# SparkFun_Thing_Plus_ESP32_WROOM_C.net
KiCad netlist of a schematic drawn in EAGLE
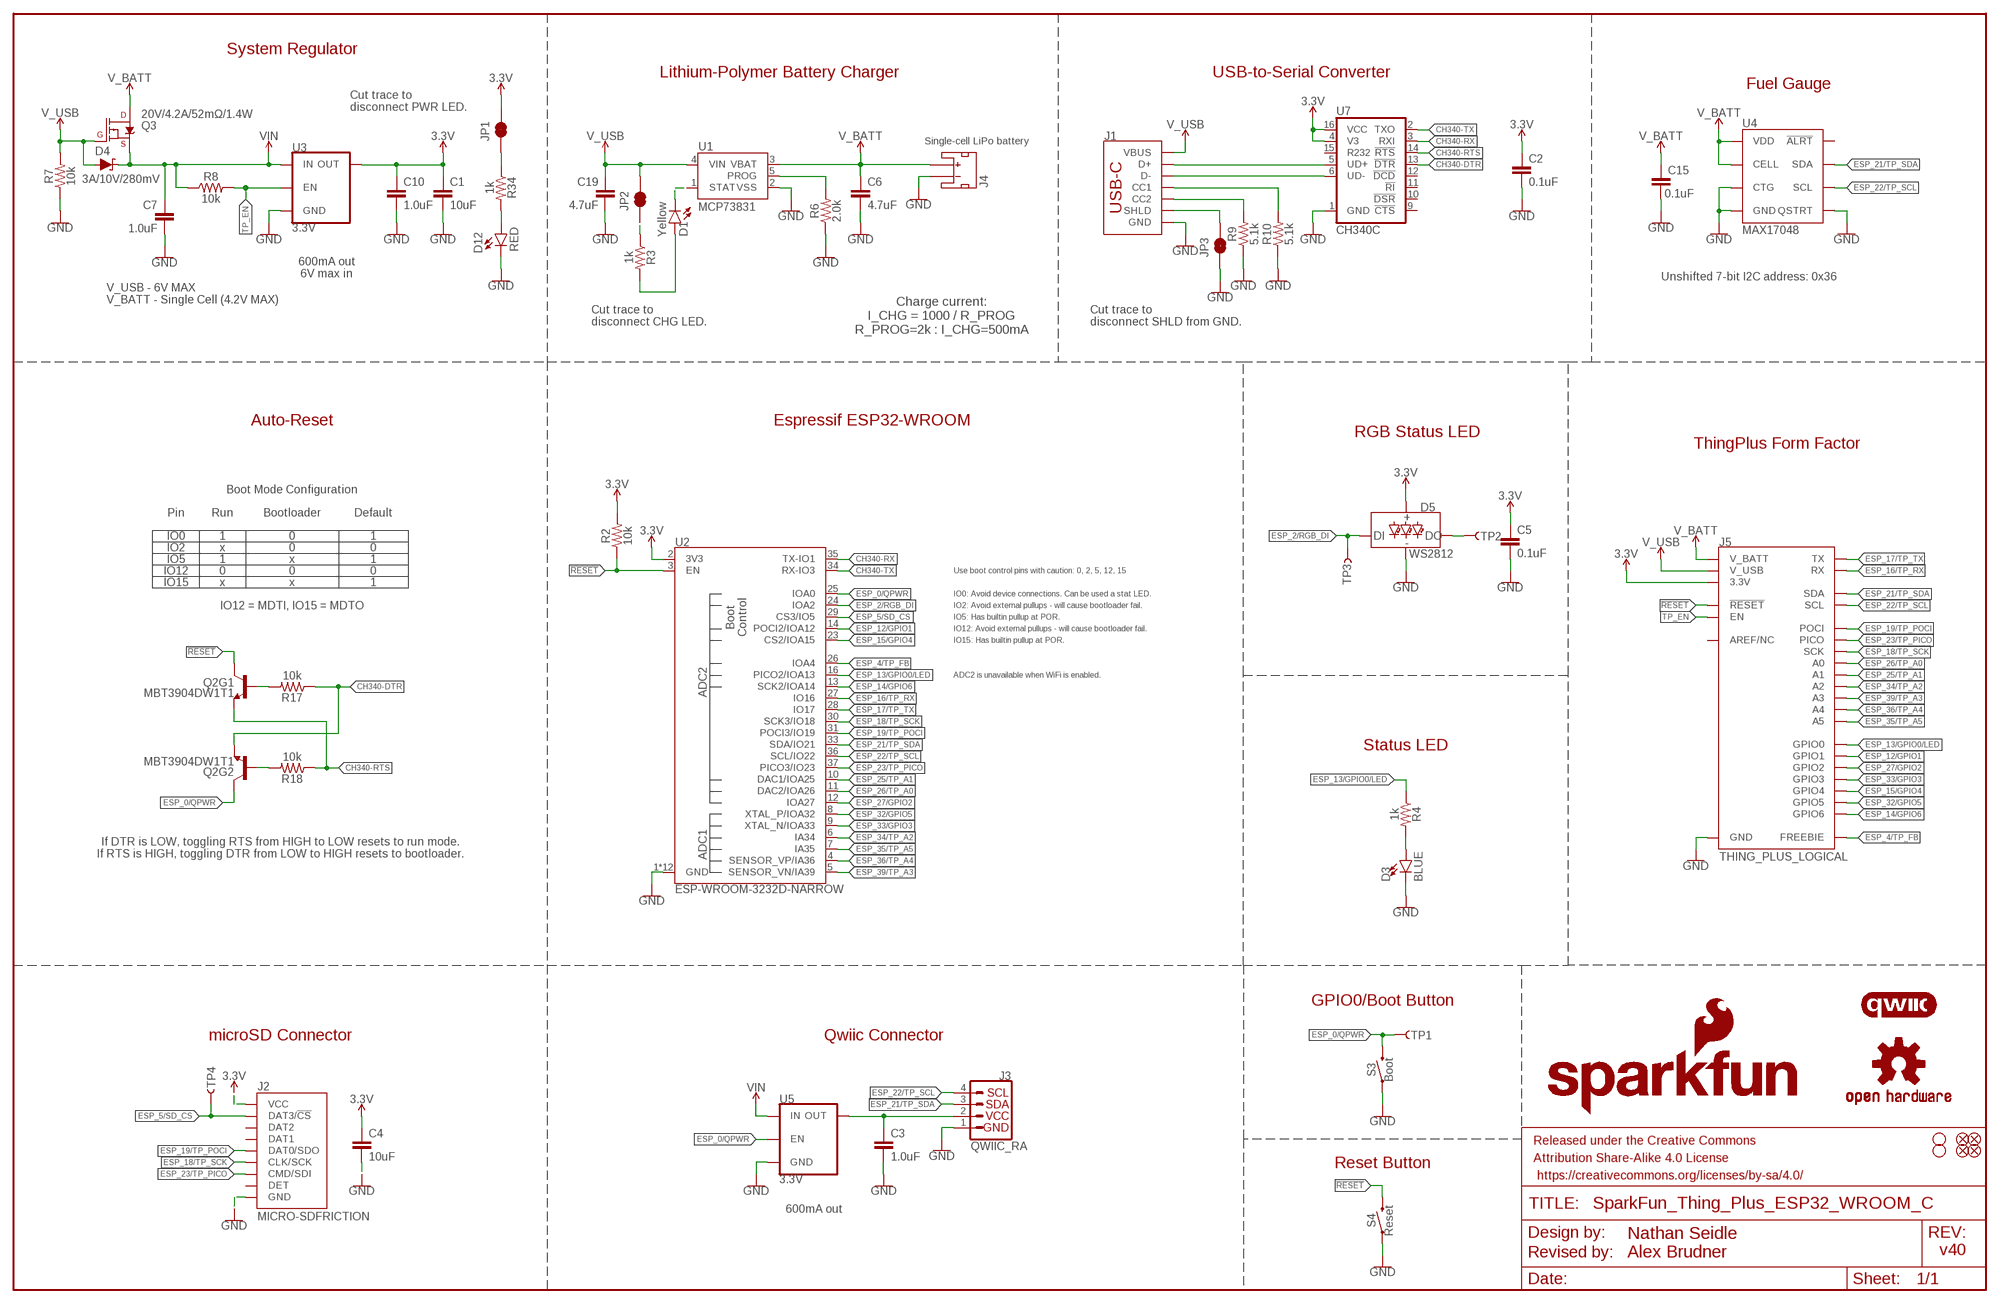
[diagram p0: schematic, sheet 1]

(export (version "E")
  (design (tool "Eeschema 10.0.6"))
  (components
    (comp (ref "C1")
      (value "10uF")
      (footprint "eagle-import:0402-TIGHT")
      (libsource (lib "eagle-import") (part "10UF-0402T-6.3V-20%"))
    )
    (comp (ref "C2")
      (value "0.1uF")
      (footprint "eagle-import:0402-TIGHT")
      (libsource (lib "eagle-import") (part "0.1UF-0402T-6.3V-10%-X7R"))
    )
    (comp (ref "C3")
      (value "1.0uF")
      (footprint "eagle-import:0402-TIGHT")
      (libsource (lib "eagle-import") (part "1.0UF-0402T-16V-10%"))
    )
    (comp (ref "C4")
      (value "10uF")
      (footprint "eagle-import:0402-TIGHT")
      (libsource (lib "eagle-import") (part "10UF-0402T-6.3V-20%"))
    )
    (comp (ref "C5")
      (value "0.1uF")
      (footprint "eagle-import:0402-TIGHT")
      (libsource (lib "eagle-import") (part "0.1UF-0402T-6.3V-10%-X7R"))
    )
    (comp (ref "C6")
      (value "4.7uF")
      (footprint "eagle-import:0402-TIGHT")
      (libsource (lib "eagle-import") (part "4.7UF-0402_TIGHT-6.3V-20%-X5R"))
    )
    (comp (ref "C7")
      (value "1.0uF")
      (footprint "eagle-import:0402-TIGHT")
      (libsource (lib "eagle-import") (part "1.0UF-0402T-16V-10%"))
    )
    (comp (ref "C10")
      (value "1.0uF")
      (footprint "eagle-import:0402-TIGHT")
      (libsource (lib "eagle-import") (part "1.0UF-0402T-16V-10%"))
    )
    (comp (ref "C15")
      (value "0.1uF")
      (footprint "eagle-import:0402-TIGHT")
      (libsource (lib "eagle-import") (part "0.1UF-0402T-16V-10%"))
    )
    (comp (ref "C19")
      (value "4.7uF")
      (footprint "eagle-import:0603")
      (libsource (lib "eagle-import") (part "4.7UF-0603-35V-(20%)"))
    )
    (comp (ref "D1")
      (value "Yellow")
      (footprint "eagle-import:LED-0603")
      (libsource (lib "eagle-import") (part "LED-YELLOW0603"))
    )
    (comp (ref "D3")
      (value "BLUE")
      (footprint "eagle-import:LED-0603")
      (libsource (lib "eagle-import") (part "LED-BLUE0603"))
    )
    (comp (ref "D4")
      (value "3A/10V/280mV")
      (footprint "eagle-import:SOD-323")
      (libsource (lib "eagle-import") (part "DIODE-SCHOTTKY-BAT60A"))
    )
    (comp (ref "D5")
      (value "WS2812")
      (footprint "eagle-import:WS2812-2020")
      (libsource (lib "eagle-import") (part "WS2812_2020"))
    )
    (comp (ref "D12")
      (value "RED")
      (footprint "eagle-import:LED-0603")
      (libsource (lib "eagle-import") (part "LED-RED0603"))
    )
    (comp (ref "FD1")
      (value "FIDUCIALUFIDUCIAL")
      (footprint "eagle-import:FIDUCIAL-MICRO")
      (libsource (lib "eagle-import") (part "FIDUCIALUFIDUCIAL"))
    )
    (comp (ref "FD2")
      (value "FIDUCIALUFIDUCIAL")
      (footprint "eagle-import:FIDUCIAL-MICRO")
      (libsource (lib "eagle-import") (part "FIDUCIALUFIDUCIAL"))
    )
    (comp (ref "FD3")
      (value "FIDUCIALUFIDUCIAL")
      (footprint "eagle-import:FIDUCIAL-MICRO")
      (libsource (lib "eagle-import") (part "FIDUCIALUFIDUCIAL"))
    )
    (comp (ref "FD4")
      (value "FIDUCIALUFIDUCIAL")
      (footprint "eagle-import:FIDUCIAL-MICRO")
      (libsource (lib "eagle-import") (part "FIDUCIALUFIDUCIAL"))
    )
    (comp (ref "FRAME1")
      (value "FRAME-LEDGER")
      (footprint "eagle-import:CREATIVE_COMMONS")
      (fields
        (field (name "DESIGNER") "Nathan Seidle")
        (field (name "REV_BY") "Revised by:")
        (field (name "REV_DES") "Alex Brudner")
      )
      (libsource (lib "eagle-import") (part "FRAME-LEDGER"))
    )
    (comp (ref "H1")
      (value "STAND-OFFTIGHT")
      (footprint "eagle-import:STAND-OFF-TIGHT")
      (libsource (lib "eagle-import") (part "STAND-OFFTIGHT"))
    )
    (comp (ref "H2")
      (value "STAND-OFFTIGHT")
      (footprint "eagle-import:STAND-OFF-TIGHT")
      (libsource (lib "eagle-import") (part "STAND-OFFTIGHT"))
    )
    (comp (ref "J1")
      (value "USB_C_2-LAYER_PADS")
      (footprint "eagle-import:USB-C-16P-2LAYER-PADS")
      (libsource (lib "eagle-import") (part "USB_C_2-LAYER_PADS"))
    )
    (comp (ref "J2")
      (value "MICRO-SDFRICTION")
      (footprint "eagle-import:MICROSD_TINY")
      (libsource (lib "eagle-import") (part "MICRO-SDFRICTION"))
    )
    (comp (ref "J3")
      (value "QWIIC_RA")
      (footprint "eagle-import:JST04_1MM_RA")
      (libsource (lib "eagle-import") (part "QWIIC_CONNECTORJS-1MM"))
    )
    (comp (ref "J4")
      (value "JST_2MM_MALE")
      (footprint "eagle-import:JST-2-SMD")
      (libsource (lib "eagle-import") (part "JST_2MM_MALE"))
    )
    (comp (ref "J5")
      (value "THING_PLUS_LOGICAL")
      (footprint "eagle-import:THING_PLUS")
      (libsource (lib "eagle-import") (part "THING_PLUS_LOGICAL"))
    )
    (comp (ref "JP1")
      (value "JUMPER-SMT_2_NC_TRACE_SILK")
      (footprint "eagle-import:SMT-JUMPER_2_NC_TRACE_SILK")
      (libsource (lib "eagle-import") (part "JUMPER-SMT_2_NC_TRACE_SILK"))
    )
    (comp (ref "JP2")
      (value "JUMPER-SMT_2_NC_TRACE_SILK")
      (footprint "eagle-import:SMT-JUMPER_2_NC_TRACE_SILK")
      (libsource (lib "eagle-import") (part "JUMPER-SMT_2_NC_TRACE_SILK"))
    )
    (comp (ref "JP3")
      (value "JUMPER-SMT_2_NC_TRACE_SILK")
      (footprint "eagle-import:SMT-JUMPER_2_NC_TRACE_SILK")
      (libsource (lib "eagle-import") (part "JUMPER-SMT_2_NC_TRACE_SILK"))
    )
    (comp (ref "LOGO1")
      (value "SFE_LOGO_NAME_FLAME.1_INCH")
      (footprint "eagle-import:SFE_LOGO_NAME_FLAME_.1")
      (libsource (lib "eagle-import") (part "SFE_LOGO_NAME_FLAME.1_INCH"))
    )
    (comp (ref "LOGO2")
      (value "OSHW-LOGOMINI")
      (footprint "eagle-import:OSHW-LOGO-MINI")
      (libsource (lib "eagle-import") (part "OSHW-LOGOMINI"))
    )
    (comp (ref "LOGO4")
      (value "QWIIC_LOGO_4MM")
      (footprint "eagle-import:QWIIC_4MM")
      (libsource (lib "eagle-import") (part "QWIIC_LOGO_4MM"))
    )
    (comp (ref "Q2")
      (value "MBT3904DW1T1")
      (footprint "eagle-import:SC70-6")
      (libsource (lib "eagle-import") (part "TRANS_NPN_DUAL-MBT3904DW1T1"))
    )
    (comp (ref "Q3")
      (value "20V/4.2A/52mΩ/1.4W")
      (footprint "eagle-import:SOT23-3")
      (libsource (lib "eagle-import") (part "MOSFET_PCH-DMG2305UX-7"))
    )
    (comp (ref "R2")
      (value "10k")
      (footprint "eagle-import:0402-TIGHT")
      (libsource (lib "eagle-import") (part "10KOHM-0402T-1/16W-1%"))
    )
    (comp (ref "R3")
      (value "1k")
      (footprint "eagle-import:0402-TIGHT")
      (libsource (lib "eagle-import") (part "1KOHM-0402T-1/16W-1%"))
    )
    (comp (ref "R4")
      (value "1k")
      (footprint "eagle-import:0402-TIGHT")
      (libsource (lib "eagle-import") (part "1KOHM-0402T-1/16W-1%"))
    )
    (comp (ref "R6")
      (value "2.0k")
      (footprint "eagle-import:0603")
      (libsource (lib "eagle-import") (part "2.0KOHM-0603-1/10W-5%"))
    )
    (comp (ref "R7")
      (value "10k")
      (footprint "eagle-import:0402-TIGHT")
      (libsource (lib "eagle-import") (part "10KOHM-0402T-1/16W-1%"))
    )
    (comp (ref "R8")
      (value "10k")
      (footprint "eagle-import:0402-TIGHT")
      (libsource (lib "eagle-import") (part "10KOHM-0402T-1/16W-1%"))
    )
    (comp (ref "R9")
      (value "5.1k")
      (footprint "eagle-import:0402-TIGHT")
      (libsource (lib "eagle-import") (part "5.1KOHM-0402T-1/16W-1%"))
    )
    (comp (ref "R10")
      (value "5.1k")
      (footprint "eagle-import:0402-TIGHT")
      (libsource (lib "eagle-import") (part "5.1KOHM-0402T-1/16W-1%"))
    )
    (comp (ref "R17")
      (value "10k")
      (footprint "eagle-import:0402-TIGHT")
      (libsource (lib "eagle-import") (part "10KOHM-0402T-1/16W-1%"))
    )
    (comp (ref "R18")
      (value "10k")
      (footprint "eagle-import:0402-TIGHT")
      (libsource (lib "eagle-import") (part "10KOHM-0402T-1/16W-1%"))
    )
    (comp (ref "R34")
      (value "1k")
      (footprint "eagle-import:0402-TIGHT")
      (libsource (lib "eagle-import") (part "1KOHM-0402T-1/16W-1%"))
    )
    (comp (ref "S3")
      (value "Boot")
      (footprint "eagle-import:TACTILE_SWITCH_SMD_4.6X2.8MM")
      (libsource (lib "eagle-import") (part "MOMENTARY-SWITCH-SPST-SMD-4.6X2.8MM"))
    )
    (comp (ref "S4")
      (value "Reset")
      (footprint "eagle-import:TACTILE_SWITCH_SMD_4.6X2.8MM")
      (libsource (lib "eagle-import") (part "MOMENTARY-SWITCH-SPST-SMD-4.6X2.8MM"))
    )
    (comp (ref "TP1")
      (value "TEST-POINT3X5")
      (footprint "eagle-import:PAD.03X.05")
      (libsource (lib "eagle-import") (part "TEST-POINT3X5"))
    )
    (comp (ref "TP2")
      (value "TEST-POINT3X5")
      (footprint "eagle-import:PAD.03X.05")
      (libsource (lib "eagle-import") (part "TEST-POINT3X5"))
    )
    (comp (ref "TP3")
      (value "TEST-POINT3X5")
      (footprint "eagle-import:PAD.03X.05")
      (libsource (lib "eagle-import") (part "TEST-POINT3X5"))
    )
    (comp (ref "TP4")
      (value "TEST-POINT3X5")
      (footprint "eagle-import:PAD.03X.05")
      (libsource (lib "eagle-import") (part "TEST-POINT3X5"))
    )
    (comp (ref "U1")
      (value "MCP73831")
      (footprint "eagle-import:SOT23-5")
      (libsource (lib "eagle-import") (part "MCP73831"))
    )
    (comp (ref "U2")
      (value "ESP-WROOM-3232D-NARROW")
      (footprint "eagle-import:ESP-WROOM-32D-NARROW")
      (libsource (lib "eagle-import") (part "ESP-WROOM-3232D-NARROW"))
    )
    (comp (ref "U3")
      (value "3.3V")
      (footprint "eagle-import:SOT23-5")
      (libsource (lib "eagle-import") (part "V_REG_AP2112K-3.3V"))
    )
    (comp (ref "U4")
      (value "MAX17048")
      (footprint "eagle-import:DFN-8")
      (libsource (lib "eagle-import") (part "MAX17048DFN8"))
    )
    (comp (ref "U5")
      (value "3.3V")
      (footprint "eagle-import:SOT23-5")
      (libsource (lib "eagle-import") (part "V_REG_AP2112K-3.3V"))
    )
    (comp (ref "U7")
      (value "CH340C")
      (footprint "eagle-import:SO016")
      (libsource (lib "eagle-import") (part "CH340C"))
    )
  )
  (nets
    (net (code "1") (name "/~{RESET}") (class "Default")
      (node (ref "J5") (pin "28") (pinfunction "~{RESET}_28") (pintype "bidirectional"))
      (node (ref "Q2") (pin "3") (pinfunction "C_3") (pintype "passive"))
      (node (ref "R2") (pin "1") (pinfunction "1_1") (pintype "passive"))
      (node (ref "S4") (pin "3") (pinfunction "2_3") (pintype "passive"))
      (node (ref "S4") (pin "4") (pinfunction "2_4") (pintype "passive"))
      (node (ref "U2") (pin "3") (pinfunction "EN_3") (pintype "bidirectional"))
    )
    (net (code "2") (name "3.3V") (class "Default")
      (node (ref "C1") (pin "1") (pinfunction "1_1") (pintype "passive"))
      (node (ref "C10") (pin "1") (pinfunction "1_1") (pintype "passive"))
      (node (ref "C2") (pin "1") (pinfunction "1_1") (pintype "passive"))
      (node (ref "C4") (pin "1") (pinfunction "1_1") (pintype "passive"))
      (node (ref "C5") (pin "1") (pinfunction "1_1") (pintype "passive"))
      (node (ref "D5") (pin "VCC") (pinfunction "VCC_VCC") (pintype "bidirectional"))
      (node (ref "J2") (pin "4") (pinfunction "VCC_4") (pintype "bidirectional"))
      (node (ref "J5") (pin "27") (pinfunction "3.3V_27") (pintype "bidirectional"))
      (node (ref "JP1") (pin "2") (pinfunction "2_2") (pintype "passive"))
      (node (ref "R2") (pin "2") (pinfunction "2_2") (pintype "passive"))
      (node (ref "U2") (pin "2") (pinfunction "3V3_2") (pintype "bidirectional"))
      (node (ref "U3") (pin "5") (pinfunction "OUT_5") (pintype "passive"))
      (node (ref "U7") (pin "16") (pinfunction "VCC_16") (pintype "bidirectional"))
      (node (ref "U7") (pin "4") (pinfunction "V3_4") (pintype "bidirectional"))
    )
    (net (code "3") (name "CH340-DTR") (class "Default")
      (node (ref "Q2") (pin "1") (pinfunction "E_1") (pintype "passive"))
      (node (ref "R17") (pin "1") (pinfunction "1_1") (pintype "passive"))
      (node (ref "U7") (pin "13") (pinfunction "~{DTR}_13") (pintype "bidirectional"))
    )
    (net (code "4") (name "CH340-RTS") (class "Default")
      (node (ref "Q2") (pin "4") (pinfunction "E_4") (pintype "passive"))
      (node (ref "R18") (pin "1") (pinfunction "1_1") (pintype "passive"))
      (node (ref "U7") (pin "14") (pinfunction "~{RTS}_14") (pintype "bidirectional"))
    )
    (net (code "5") (name "CH340-RX") (class "Default")
      (node (ref "U2") (pin "35") (pinfunction "TX-IO1_35") (pintype "bidirectional"))
      (node (ref "U7") (pin "3") (pinfunction "RXI_3") (pintype "bidirectional"))
    )
    (net (code "6") (name "CH340-TX") (class "Default")
      (node (ref "U2") (pin "34") (pinfunction "RX-IO3_34") (pintype "bidirectional"))
      (node (ref "U7") (pin "2") (pinfunction "TXO_2") (pintype "bidirectional"))
    )
    (net (code "7") (name "ESP_0{slash}QPWR") (class "Default")
      (node (ref "Q2") (pin "6") (pinfunction "C_6") (pintype "passive"))
      (node (ref "S3") (pin "3") (pinfunction "2_3") (pintype "passive"))
      (node (ref "S3") (pin "4") (pinfunction "2_4") (pintype "passive"))
      (node (ref "TP1") (pin "1") (pinfunction "1_1") (pintype "bidirectional"))
      (node (ref "U2") (pin "25") (pinfunction "IOA0_25") (pintype "bidirectional"))
      (node (ref "U5") (pin "3") (pinfunction "EN_3") (pintype "input"))
    )
    (net (code "8") (name "ESP_2{slash}RGB_DI") (class "Default")
      (node (ref "D5") (pin "DI") (pinfunction "DI_DI") (pintype "bidirectional"))
      (node (ref "TP3") (pin "1") (pinfunction "1_1") (pintype "bidirectional"))
      (node (ref "U2") (pin "24") (pinfunction "IOA2_24") (pintype "bidirectional"))
    )
    (net (code "9") (name "ESP_4{slash}TP_FB") (class "Default")
      (node (ref "J5") (pin "13") (pinfunction "FREEBIE_13") (pintype "bidirectional"))
      (node (ref "U2") (pin "26") (pinfunction "IOA4_26") (pintype "bidirectional"))
    )
    (net (code "10") (name "ESP_5{slash}SD_CS") (class "Default")
      (node (ref "J2") (pin "2") (pinfunction "DAT3/~{CS}_2") (pintype "bidirectional"))
      (node (ref "TP4") (pin "1") (pinfunction "1_1") (pintype "bidirectional"))
      (node (ref "U2") (pin "29") (pinfunction "CS3/IO5_29") (pintype "bidirectional"))
    )
    (net (code "11") (name "ESP_12{slash}GPIO1") (class "Default")
      (node (ref "J5") (pin "8") (pinfunction "GPIO1_8") (pintype "bidirectional"))
      (node (ref "U2") (pin "14") (pinfunction "POCI2/IOA12_14") (pintype "bidirectional"))
    )
    (net (code "12") (name "ESP_13{slash}GPIO0{slash}LED") (class "Default")
      (node (ref "J5") (pin "9") (pinfunction "GPIO0_9") (pintype "bidirectional"))
      (node (ref "R4") (pin "1") (pinfunction "1_1") (pintype "passive"))
      (node (ref "U2") (pin "16") (pinfunction "PICO2/IOA13_16") (pintype "bidirectional"))
    )
    (net (code "13") (name "ESP_14{slash}GPIO6") (class "Default")
      (node (ref "J5") (pin "3") (pinfunction "GPIO6_3") (pintype "bidirectional"))
      (node (ref "U2") (pin "13") (pinfunction "SCK2/IOA14_13") (pintype "bidirectional"))
    )
    (net (code "14") (name "ESP_15{slash}GPIO4") (class "Default")
      (node (ref "J5") (pin "5") (pinfunction "GPIO4_5") (pintype "bidirectional"))
      (node (ref "U2") (pin "23") (pinfunction "CS2/IOA15_23") (pintype "bidirectional"))
    )
    (net (code "15") (name "ESP_16{slash}TP_RX") (class "Default")
      (node (ref "J5") (pin "15") (pinfunction "RX_15") (pintype "bidirectional"))
      (node (ref "U2") (pin "27") (pinfunction "IO16_27") (pintype "bidirectional"))
    )
    (net (code "16") (name "ESP_17{slash}TP_TX") (class "Default")
      (node (ref "J5") (pin "14") (pinfunction "TX_14") (pintype "bidirectional"))
      (node (ref "U2") (pin "28") (pinfunction "IO17_28") (pintype "bidirectional"))
    )
    (net (code "17") (name "ESP_18{slash}TP_SCK") (class "Default")
      (node (ref "J2") (pin "5") (pinfunction "CLK/SCK_5") (pintype "bidirectional"))
      (node (ref "J5") (pin "18") (pinfunction "SCK_18") (pintype "bidirectional"))
      (node (ref "U2") (pin "30") (pinfunction "SCK3/IO18_30") (pintype "bidirectional"))
    )
    (net (code "18") (name "ESP_19{slash}TP_POCI") (class "Default")
      (node (ref "J2") (pin "7") (pinfunction "DAT0/SDO_7") (pintype "bidirectional"))
      (node (ref "J5") (pin "16") (pinfunction "POCI_16") (pintype "bidirectional"))
      (node (ref "U2") (pin "31") (pinfunction "POCI3/IO19_31") (pintype "bidirectional"))
    )
    (net (code "19") (name "ESP_21{slash}TP_SDA") (class "Default")
      (node (ref "J3") (pin "3") (pinfunction "3_3") (pintype "passive"))
      (node (ref "J5") (pin "1") (pinfunction "SDA_1") (pintype "bidirectional"))
      (node (ref "U2") (pin "33") (pinfunction "SDA/IO21_33") (pintype "bidirectional"))
      (node (ref "U4") (pin "8") (pinfunction "SDA_8") (pintype "input"))
    )
    (net (code "20") (name "ESP_22{slash}TP_SCL") (class "Default")
      (node (ref "J3") (pin "4") (pinfunction "4_4") (pintype "passive"))
      (node (ref "J5") (pin "2") (pinfunction "SCL_2") (pintype "bidirectional"))
      (node (ref "U2") (pin "36") (pinfunction "SCL/IO22_36") (pintype "bidirectional"))
      (node (ref "U4") (pin "7") (pinfunction "SCL_7") (pintype "output"))
    )
    (net (code "21") (name "ESP_23{slash}TP_PICO") (class "Default")
      (node (ref "J2") (pin "3") (pinfunction "CMD/SDI_3") (pintype "bidirectional"))
      (node (ref "J5") (pin "17") (pinfunction "PICO_17") (pintype "bidirectional"))
      (node (ref "U2") (pin "37") (pinfunction "PICO3/IO23_37") (pintype "bidirectional"))
    )
    (net (code "22") (name "ESP_25{slash}TP_A1") (class "Default")
      (node (ref "J5") (pin "23") (pinfunction "A1_23") (pintype "bidirectional"))
      (node (ref "U2") (pin "10") (pinfunction "DAC1/IOA25_10") (pintype "bidirectional"))
    )
    (net (code "23") (name "ESP_26{slash}TP_A0") (class "Default")
      (node (ref "J5") (pin "24") (pinfunction "A0_24") (pintype "bidirectional"))
      (node (ref "U2") (pin "11") (pinfunction "DAC2/IOA26_11") (pintype "bidirectional"))
    )
    (net (code "24") (name "ESP_27{slash}GPIO2") (class "Default")
      (node (ref "J5") (pin "7") (pinfunction "GPIO2_7") (pintype "bidirectional"))
      (node (ref "U2") (pin "12") (pinfunction "IOA27_12") (pintype "bidirectional"))
    )
    (net (code "25") (name "ESP_32{slash}GPIO5") (class "Default")
      (node (ref "J5") (pin "4") (pinfunction "GPIO5_4") (pintype "bidirectional"))
      (node (ref "U2") (pin "8") (pinfunction "XTAL_P/IOA32_8") (pintype "bidirectional"))
    )
    (net (code "26") (name "ESP_33{slash}GPIO3") (class "Default")
      (node (ref "J5") (pin "6") (pinfunction "GPIO3_6") (pintype "bidirectional"))
      (node (ref "U2") (pin "9") (pinfunction "XTAL_N/IOA33_9") (pintype "bidirectional"))
    )
    (net (code "27") (name "ESP_34{slash}TP_A2") (class "Default")
      (node (ref "J5") (pin "22") (pinfunction "A2_22") (pintype "bidirectional"))
      (node (ref "U2") (pin "6") (pinfunction "IA34_6") (pintype "bidirectional"))
    )
    (net (code "28") (name "ESP_35{slash}TP_A5") (class "Default")
      (node (ref "J5") (pin "19") (pinfunction "A5_19") (pintype "bidirectional"))
      (node (ref "U2") (pin "7") (pinfunction "IA35_7") (pintype "bidirectional"))
    )
    (net (code "29") (name "ESP_36{slash}TP_A4") (class "Default")
      (node (ref "J5") (pin "20") (pinfunction "A4_20") (pintype "bidirectional"))
      (node (ref "U2") (pin "4") (pinfunction "SENSOR_VP/IA36_4") (pintype "bidirectional"))
    )
    (net (code "30") (name "ESP_39{slash}TP_A3") (class "Default")
      (node (ref "J5") (pin "21") (pinfunction "A3_21") (pintype "bidirectional"))
      (node (ref "U2") (pin "5") (pinfunction "SENSOR_VN/IA39_5") (pintype "bidirectional"))
    )
    (net (code "31") (name "GND") (class "Default")
      (node (ref "C1") (pin "2") (pinfunction "2_2") (pintype "passive"))
      (node (ref "C10") (pin "2") (pinfunction "2_2") (pintype "passive"))
      (node (ref "C15") (pin "2") (pinfunction "2_2") (pintype "passive"))
      (node (ref "C19") (pin "2") (pinfunction "2_2") (pintype "passive"))
      (node (ref "C2") (pin "2") (pinfunction "2_2") (pintype "passive"))
      (node (ref "C3") (pin "2") (pinfunction "2_2") (pintype "passive"))
      (node (ref "C4") (pin "2") (pinfunction "2_2") (pintype "passive"))
      (node (ref "C5") (pin "2") (pinfunction "2_2") (pintype "passive"))
      (node (ref "C6") (pin "2") (pinfunction "2_2") (pintype "passive"))
      (node (ref "C7") (pin "2") (pinfunction "2_2") (pintype "passive"))
      (node (ref "D12") (pin "C") (pinfunction "C_C") (pintype "passive"))
      (node (ref "D3") (pin "C") (pinfunction "C_C") (pintype "passive"))
      (node (ref "D5") (pin "GND") (pinfunction "GND_GND") (pintype "bidirectional"))
      (node (ref "J1") (pin "GND") (pinfunction "GND_GND") (pintype "bidirectional"))
      (node (ref "J1") (pin "GND2") (pinfunction "GND_GND2") (pintype "bidirectional"))
      (node (ref "J2") (pin "6") (pinfunction "GND_6") (pintype "bidirectional"))
      (node (ref "J2") (pin "GND1") (pinfunction "GND_GND1") (pintype "bidirectional"))
      (node (ref "J2") (pin "GND2") (pinfunction "GND_GND2") (pintype "bidirectional"))
      (node (ref "J2") (pin "GND3") (pinfunction "GND_GND3") (pintype "bidirectional"))
      (node (ref "J2") (pin "GND4") (pinfunction "GND_GND4") (pintype "bidirectional"))
      (node (ref "J2") (pin "GND5") (pinfunction "GND_GND5") (pintype "bidirectional"))
      (node (ref "J2") (pin "GND6") (pinfunction "GND_GND6") (pintype "bidirectional"))
      (node (ref "J3") (pin "1") (pinfunction "1_1") (pintype "power_in"))
      (node (ref "J4") (pin "1") (pinfunction "-_1") (pintype "bidirectional"))
      (node (ref "J5") (pin "25") (pinfunction "GND_25") (pintype "bidirectional"))
      (node (ref "JP3") (pin "1") (pinfunction "1_1") (pintype "passive"))
      (node (ref "R10") (pin "1") (pinfunction "1_1") (pintype "passive"))
      (node (ref "R6") (pin "1") (pinfunction "1_1") (pintype "passive"))
      (node (ref "R7") (pin "1") (pinfunction "1_1") (pintype "passive"))
      (node (ref "R9") (pin "1") (pinfunction "1_1") (pintype "passive"))
      (node (ref "S3") (pin "1") (pinfunction "1_1") (pintype "passive"))
      (node (ref "S3") (pin "2") (pinfunction "1_2") (pintype "passive"))
      (node (ref "S4") (pin "1") (pinfunction "1_1") (pintype "passive"))
      (node (ref "S4") (pin "2") (pinfunction "1_2") (pintype "passive"))
      (node (ref "U1") (pin "2") (pinfunction "VSS_2") (pintype "power_in"))
      (node (ref "U2") (pin "1") (pinfunction "GND_1") (pintype "bidirectional"))
      (node (ref "U2") (pin "15") (pinfunction "GND_15") (pintype "bidirectional"))
      (node (ref "U2") (pin "38") (pinfunction "GND_38") (pintype "bidirectional"))
      (node (ref "U2") (pin "GND1") (pinfunction "GND_GND1") (pintype "bidirectional"))
      (node (ref "U2") (pin "GNDT1") (pinfunction "GND_GNDT1") (pintype "bidirectional"))
      (node (ref "U2") (pin "GNDT2") (pinfunction "GND_GNDT2") (pintype "bidirectional"))
      (node (ref "U2") (pin "GNDT3") (pinfunction "GND_GNDT3") (pintype "bidirectional"))
      (node (ref "U2") (pin "GNDT4") (pinfunction "GND_GNDT4") (pintype "bidirectional"))
      (node (ref "U2") (pin "GNDT5") (pinfunction "GND_GNDT5") (pintype "bidirectional"))
      (node (ref "U2") (pin "GNDT6") (pinfunction "GND_GNDT6") (pintype "bidirectional"))
      (node (ref "U2") (pin "GNDT7") (pinfunction "GND_GNDT7") (pintype "bidirectional"))
      (node (ref "U2") (pin "GNDT8") (pinfunction "GND_GNDT8") (pintype "bidirectional"))
      (node (ref "U3") (pin "2") (pinfunction "GND_2") (pintype "input"))
      (node (ref "U4") (pin "1") (pinfunction "CTG_1") (pintype "input"))
      (node (ref "U4") (pin "4") (pinfunction "GND_4") (pintype "bidirectional"))
      (node (ref "U4") (pin "6") (pinfunction "QSTRT_6") (pintype "bidirectional"))
      (node (ref "U4") (pin "9") (pinfunction "GND_9") (pintype "bidirectional"))
      (node (ref "U5") (pin "2") (pinfunction "GND_2") (pintype "input"))
      (node (ref "U7") (pin "1") (pinfunction "GND_1") (pintype "bidirectional"))
    )
    (net (code "32") (name "Net-(D1-PadA)") (class "Default")
      (node (ref "D1") (pin "A") (pinfunction "A_A") (pintype "passive"))
      (node (ref "R3") (pin "2") (pinfunction "2_2") (pintype "passive"))
    )
    (net (code "33") (name "Net-(D3-PadA)") (class "Default")
      (node (ref "D3") (pin "A") (pinfunction "A_A") (pintype "passive"))
      (node (ref "R4") (pin "2") (pinfunction "2_2") (pintype "passive"))
    )
    (net (code "34") (name "Net-(D5-PadDO)") (class "Default")
      (node (ref "D5") (pin "DO") (pinfunction "DO_DO") (pintype "bidirectional"))
      (node (ref "TP2") (pin "1") (pinfunction "1_1") (pintype "bidirectional"))
    )
    (net (code "35") (name "Net-(D12-PadA)") (class "Default")
      (node (ref "D12") (pin "A") (pinfunction "A_A") (pintype "passive"))
      (node (ref "R34") (pin "2") (pinfunction "2_2") (pintype "passive"))
    )
    (net (code "36") (name "Net-(J1-CC1)") (class "Default")
      (node (ref "J1") (pin "A5") (pinfunction "CC1_A5") (pintype "bidirectional"))
      (node (ref "R10") (pin "2") (pinfunction "2_2") (pintype "passive"))
    )
    (net (code "37") (name "Net-(J1-CC2)") (class "Default")
      (node (ref "J1") (pin "B5") (pinfunction "CC2_B5") (pintype "bidirectional"))
      (node (ref "R9") (pin "2") (pinfunction "2_2") (pintype "passive"))
    )
    (net (code "38") (name "Net-(J1-SHLD-PadSHLD1)") (class "Default")
      (node (ref "J1") (pin "SHLD1") (pinfunction "SHLD_SHLD1") (pintype "bidirectional"))
      (node (ref "J1") (pin "SHLD2") (pinfunction "SHLD_SHLD2") (pintype "bidirectional"))
      (node (ref "J1") (pin "SHLD3") (pinfunction "SHLD_SHLD3") (pintype "bidirectional"))
      (node (ref "J1") (pin "SHLD4") (pinfunction "SHLD_SHLD4") (pintype "bidirectional"))
      (node (ref "JP3") (pin "2") (pinfunction "2_2") (pintype "passive"))
    )
    (net (code "39") (name "Net-(JP1-Pad1)") (class "Default")
      (node (ref "JP1") (pin "1") (pinfunction "1_1") (pintype "passive"))
      (node (ref "R34") (pin "1") (pinfunction "1_1") (pintype "passive"))
    )
    (net (code "40") (name "Net-(JP2-Pad1)") (class "Default")
      (node (ref "JP2") (pin "1") (pinfunction "1_1") (pintype "passive"))
      (node (ref "R3") (pin "1") (pinfunction "1_1") (pintype "passive"))
    )
    (net (code "41") (name "Net-(Q2A-B)") (class "Default")
      (node (ref "Q2") (pin "5") (pinfunction "B_5") (pintype "passive"))
      (node (ref "R17") (pin "2") (pinfunction "2_2") (pintype "passive"))
    )
    (net (code "42") (name "Net-(Q2B-B)") (class "Default")
      (node (ref "Q2") (pin "2") (pinfunction "B_2") (pintype "passive"))
      (node (ref "R18") (pin "2") (pinfunction "2_2") (pintype "passive"))
    )
    (net (code "43") (name "Net-(U1-PROG)") (class "Default")
      (node (ref "R6") (pin "2") (pinfunction "2_2") (pintype "passive"))
      (node (ref "U1") (pin "5") (pinfunction "PROG_5") (pintype "input"))
    )
    (net (code "44") (name "Net-(U1-STAT)") (class "Default")
      (node (ref "D1") (pin "C") (pinfunction "C_C") (pintype "passive"))
      (node (ref "U1") (pin "1") (pinfunction "STAT_1") (pintype "output"))
    )
    (net (code "45") (name "Net-(U5-OUT)") (class "Default")
      (node (ref "C3") (pin "1") (pinfunction "1_1") (pintype "passive"))
      (node (ref "J3") (pin "2") (pinfunction "2_2") (pintype "power_in"))
      (node (ref "U5") (pin "5") (pinfunction "OUT_5") (pintype "passive"))
    )
    (net (code "46") (name "Net-(U7-UD+)") (class "Default")
      (node (ref "J1") (pin "A6") (pinfunction "D+_A6") (pintype "bidirectional"))
      (node (ref "J1") (pin "B6") (pinfunction "D+_B6") (pintype "bidirectional"))
      (node (ref "U7") (pin "5") (pinfunction "UD+_5") (pintype "bidirectional"))
    )
    (net (code "47") (name "Net-(U7-UD-)") (class "Default")
      (node (ref "J1") (pin "A7") (pinfunction "D-_A7") (pintype "bidirectional"))
      (node (ref "J1") (pin "B7") (pinfunction "D-_B7") (pintype "bidirectional"))
      (node (ref "U7") (pin "6") (pinfunction "UD-_6") (pintype "bidirectional"))
    )
    (net (code "48") (name "TP_EN") (class "Default")
      (node (ref "J5") (pin "11") (pinfunction "EN_11") (pintype "bidirectional"))
      (node (ref "R8") (pin "2") (pinfunction "2_2") (pintype "passive"))
      (node (ref "U3") (pin "3") (pinfunction "EN_3") (pintype "input"))
    )
    (net (code "49") (name "VIN") (class "Default")
      (node (ref "C7") (pin "1") (pinfunction "1_1") (pintype "passive"))
      (node (ref "D4") (pin "C") (pinfunction "C_C") (pintype "passive"))
      (node (ref "Q3") (pin "2") (pinfunction "S_2") (pintype "bidirectional"))
      (node (ref "R8") (pin "1") (pinfunction "1_1") (pintype "passive"))
      (node (ref "U3") (pin "1") (pinfunction "IN_1") (pintype "input"))
      (node (ref "U5") (pin "1") (pinfunction "IN_1") (pintype "input"))
    )
    (net (code "50") (name "V_BATT") (class "Default")
      (node (ref "C15") (pin "1") (pinfunction "1_1") (pintype "passive"))
      (node (ref "C6") (pin "1") (pinfunction "1_1") (pintype "passive"))
      (node (ref "J4") (pin "2") (pinfunction "+_2") (pintype "bidirectional"))
      (node (ref "J5") (pin "12") (pinfunction "V_BATT_12") (pintype "bidirectional"))
      (node (ref "Q3") (pin "3") (pinfunction "D_3") (pintype "bidirectional"))
      (node (ref "U1") (pin "3") (pinfunction "VBAT_3") (pintype "power_in"))
      (node (ref "U4") (pin "2") (pinfunction "CELL_2") (pintype "input"))
      (node (ref "U4") (pin "3") (pinfunction "VDD_3") (pintype "bidirectional"))
    )
    (net (code "51") (name "V_USB") (class "Default")
      (node (ref "C19") (pin "1") (pinfunction "1_1") (pintype "passive"))
      (node (ref "D4") (pin "A") (pinfunction "A_A") (pintype "passive"))
      (node (ref "J1") (pin "VBUS1") (pinfunction "VBUS_VBUS1") (pintype "bidirectional"))
      (node (ref "J1") (pin "VBUS2") (pinfunction "VBUS_VBUS2") (pintype "bidirectional"))
      (node (ref "J5") (pin "10") (pinfunction "V_USB_10") (pintype "bidirectional"))
      (node (ref "JP2") (pin "2") (pinfunction "2_2") (pintype "passive"))
      (node (ref "Q3") (pin "1") (pinfunction "G_1") (pintype "bidirectional"))
      (node (ref "R7") (pin "2") (pinfunction "2_2") (pintype "passive"))
      (node (ref "U1") (pin "4") (pinfunction "VIN_4") (pintype "power_in"))
    )
    (net (code "52") (name "unconnected-(J2-DAT1-Pad8)") (class "Default")
      (node (ref "J2") (pin "8") (pinfunction "DAT1_8") (pintype "bidirectional"))
    )
    (net (code "53") (name "unconnected-(J2-DAT2-Pad1)") (class "Default")
      (node (ref "J2") (pin "1") (pinfunction "DAT2_1") (pintype "bidirectional"))
    )
    (net (code "54") (name "unconnected-(J2-DET-Pad9)") (class "Default")
      (node (ref "J2") (pin "9") (pinfunction "DET_9") (pintype "bidirectional"))
    )
    (net (code "55") (name "unconnected-(J4-PAD1-PadNC1)") (class "Default")
      (node (ref "J4") (pin "NC1") (pinfunction "PAD1_NC1") (pintype "bidirectional"))
    )
    (net (code "56") (name "unconnected-(J4-PAD2-PadNC2)") (class "Default")
      (node (ref "J4") (pin "NC2") (pinfunction "PAD2_NC2") (pintype "bidirectional"))
    )
    (net (code "57") (name "unconnected-(J5-AREF{slash}NC-Pad26)") (class "Default")
      (node (ref "J5") (pin "26") (pinfunction "AREF/NC_26") (pintype "bidirectional"))
    )
    (net (code "58") (name "unconnected-(U4-~{ALRT}-Pad5)") (class "Default")
      (node (ref "U4") (pin "5") (pinfunction "~{ALRT}_5") (pintype "bidirectional"))
    )
    (net (code "59") (name "unconnected-(U7-R232-Pad15)") (class "Default")
      (node (ref "U7") (pin "15") (pinfunction "R232_15") (pintype "bidirectional"))
    )
    (net (code "60") (name "unconnected-(U7-~{CTS}-Pad9)") (class "Default")
      (node (ref "U7") (pin "9") (pinfunction "~{CTS}_9") (pintype "bidirectional"))
    )
    (net (code "61") (name "unconnected-(U7-~{DCD}-Pad12)") (class "Default")
      (node (ref "U7") (pin "12") (pinfunction "~{DCD}_12") (pintype "bidirectional"))
    )
    (net (code "62") (name "unconnected-(U7-~{DSR}-Pad10)") (class "Default")
      (node (ref "U7") (pin "10") (pinfunction "~{DSR}_10") (pintype "bidirectional"))
    )
    (net (code "63") (name "unconnected-(U7-~{RI}-Pad11)") (class "Default")
      (node (ref "U7") (pin "11") (pinfunction "~{RI}_11") (pintype "bidirectional"))
    )
  )
)
